# STorM32_NT_logger_v10.net
KiCad netlist of a schematic drawn in EAGLE
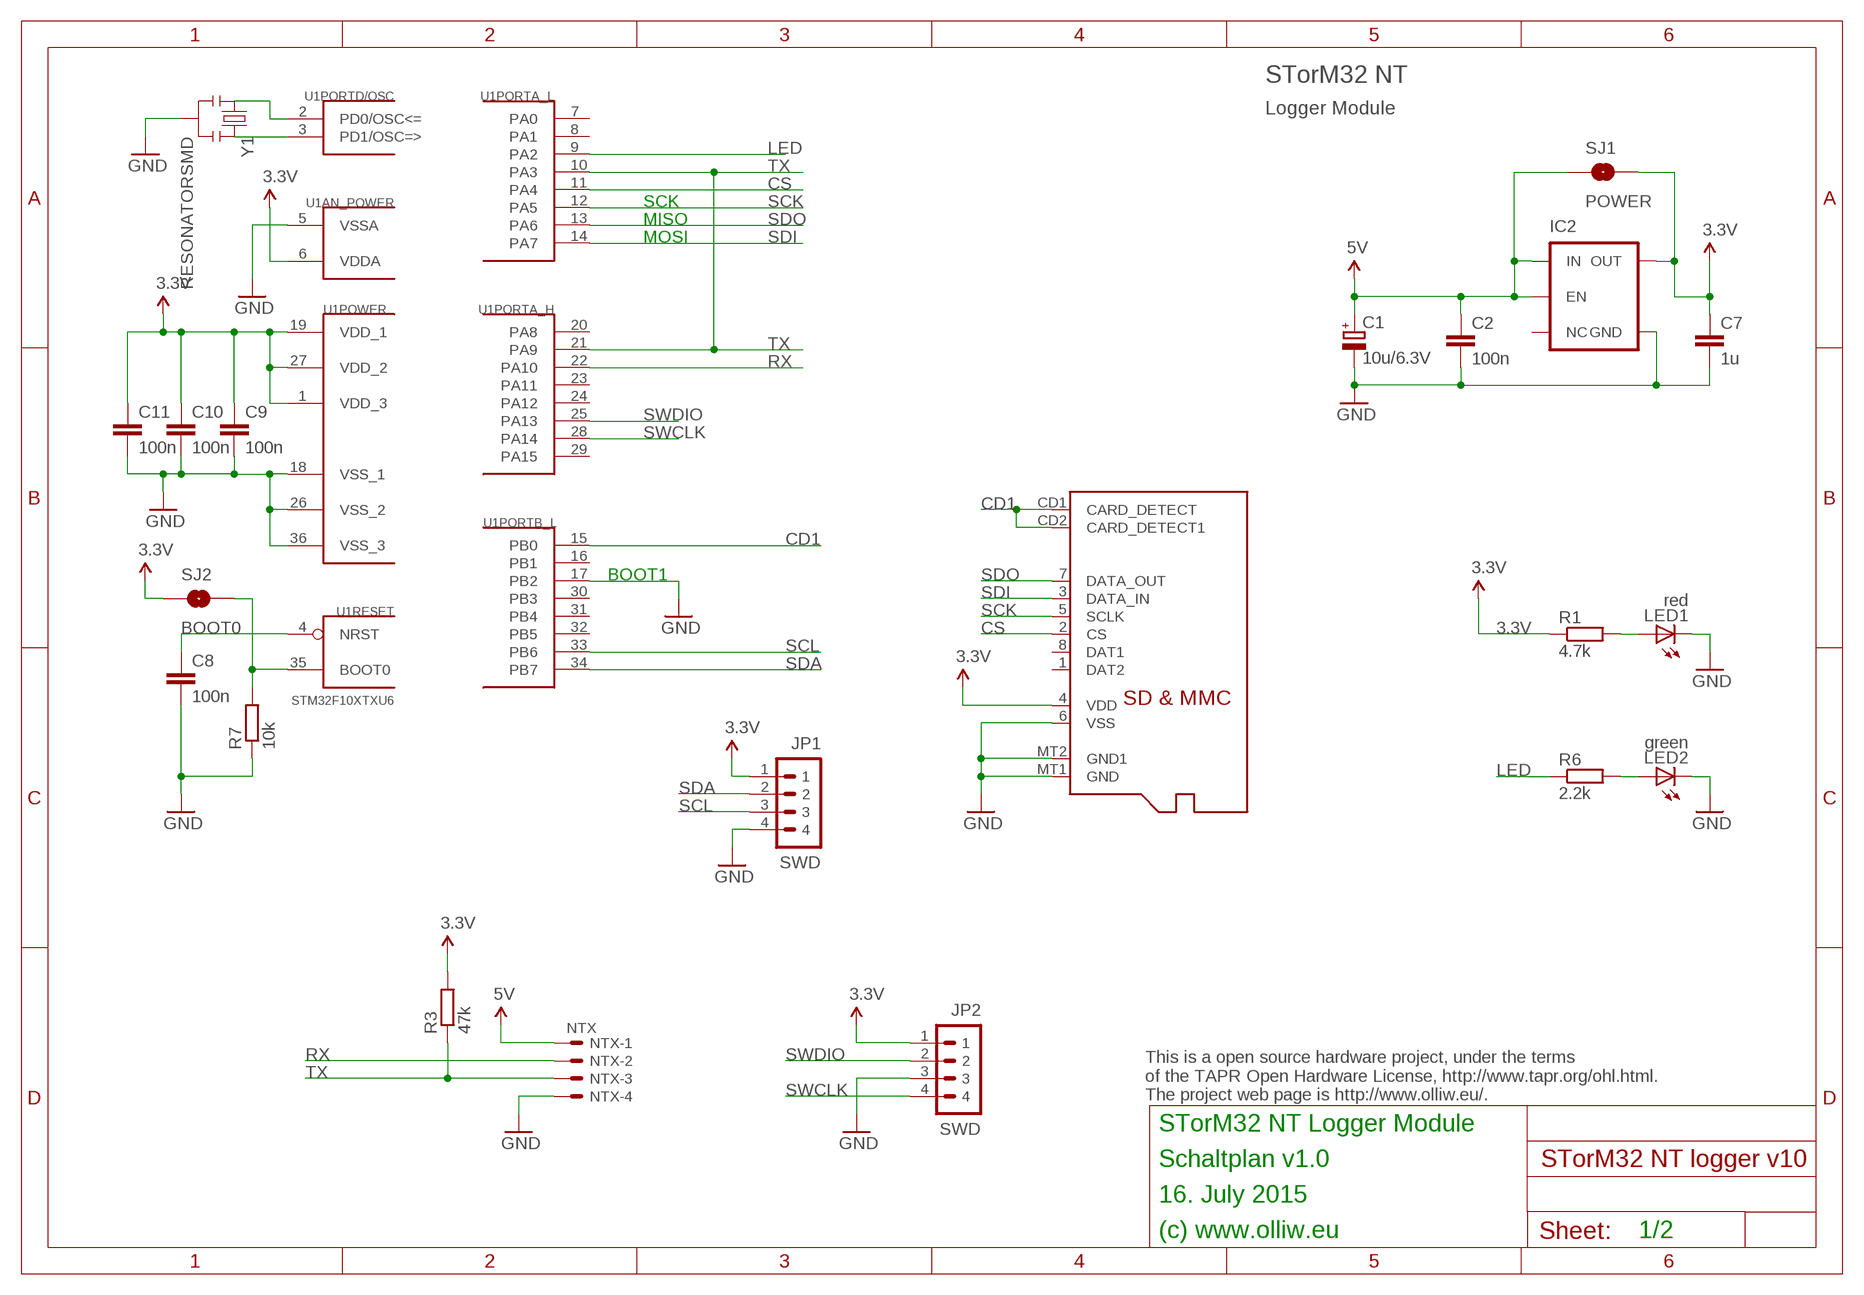
[diagram p0: schematic, sheet 1]

(export (version "E")
  (design (tool "Eeschema 10.0.6"))
  (components
    (comp (ref "C1")
      (value "10u/6.3V")
      (footprint "eagle-import:SMC_B")
      (libsource (lib "eagle-import") (part "CPOL-EUSMCB"))
    )
    (comp (ref "C2")
      (value "100n")
      (footprint "eagle-import:C0603")
      (libsource (lib "eagle-import") (part "C-EUC0603"))
    )
    (comp (ref "C7")
      (value "1u")
      (footprint "eagle-import:C0603")
      (libsource (lib "eagle-import") (part "C-EUC0603"))
    )
    (comp (ref "C8")
      (value "100n")
      (footprint "eagle-import:C0603")
      (libsource (lib "eagle-import") (part "C-EUC0603"))
    )
    (comp (ref "C9")
      (value "100n")
      (footprint "eagle-import:C0603")
      (libsource (lib "eagle-import") (part "C-EUC0603"))
    )
    (comp (ref "C10")
      (value "100n")
      (footprint "eagle-import:C0603")
      (libsource (lib "eagle-import") (part "C-EUC0603"))
    )
    (comp (ref "C11")
      (value "100n")
      (footprint "eagle-import:C0603")
      (libsource (lib "eagle-import") (part "C-EUC0603"))
    )
    (comp (ref "IC2")
      (value "V_REG_TPS76433SOT23-5")
      (footprint "eagle-import:SOT23-5")
      (libsource (lib "eagle-import") (part "V_REG_TPS76433SOT23-5"))
    )
    (comp (ref "JP1")
      (value "SWD")
      (footprint "eagle-import:4X1_1P27_OCT_BILEX")
      (libsource (lib "eagle-import") (part "P4X1_1P27-OCT_BILEX"))
    )
    (comp (ref "JP2")
      (value "SWD")
      (footprint "eagle-import:4X1_1P27_OCT_BILEX")
      (libsource (lib "eagle-import") (part "P4X1_1P27-OCT_BILEX"))
    )
    (comp (ref "LED1")
      (value "red")
      (footprint "eagle-import:CHIPLED_0603")
      (libsource (lib "eagle-import") (part "LEDCHIPLED_0603"))
    )
    (comp (ref "LED2")
      (value "green")
      (footprint "eagle-import:CHIPLED_0603")
      (libsource (lib "eagle-import") (part "LEDCHIPLED_0603"))
    )
    (comp (ref "NTX")
      (value "NTX")
      (footprint "eagle-import:SM04B-SRSS-TB")
      (libsource (lib "eagle-import") (part "?M04B-SRSS-TBS"))
    )
    (comp (ref "R1")
      (value "4.7k")
      (footprint "eagle-import:R0603")
      (libsource (lib "eagle-import") (part "R-EU_R0603"))
    )
    (comp (ref "R3")
      (value "47k")
      (footprint "eagle-import:R0603")
      (libsource (lib "eagle-import") (part "R-EU_R0603"))
    )
    (comp (ref "R6")
      (value "2.2k")
      (footprint "eagle-import:R0603")
      (libsource (lib "eagle-import") (part "R-EU_R0603"))
    )
    (comp (ref "R7")
      (value "10k")
      (footprint "eagle-import:R0603")
      (libsource (lib "eagle-import") (part "R-EU_R0603"))
    )
    (comp (ref "SJ1")
      (value "POWER")
      (footprint "eagle-import:SJ_2S-NO")
      (libsource (lib "eagle-import") (part "SOLDERJUMPERNO"))
    )
    (comp (ref "SJ2")
      (value "BOOT0")
      (footprint "eagle-import:SJ_2S-NO")
      (libsource (lib "eagle-import") (part "SOLDERJUMPERNO"))
    )
    (comp (ref "U$1")
      (value "MICROSD")
      (footprint "eagle-import:MICROSD")
      (libsource (lib "eagle-import") (part "MICROSD"))
    )
    (comp (ref "U1")
      (value "STM32F10XTXU6")
      (footprint "eagle-import:VFQFPN36")
      (libsource (lib "eagle-import") (part "STM32F10XTXU6"))
    )
    (comp (ref "Y1")
      (value "RESONATORSMD")
      (footprint "eagle-import:RESONATOR-SMD")
      (libsource (lib "eagle-import") (part "RESONATORSMD"))
    )
  )
  (nets
    (net (code "1") (name "/CD1") (class "Default")
      (node (ref "U$1") (pin "CD1") (pinfunction "CARD_DETECT_CD1") (pintype "passive"))
      (node (ref "U$1") (pin "CD2") (pinfunction "CARD_DETECT1_CD2") (pintype "passive"))
      (node (ref "U1") (pin "15") (pinfunction "PB0_15") (pintype "bidirectional"))
    )
    (net (code "2") (name "/CS") (class "Default")
      (node (ref "U$1") (pin "2") (pinfunction "CS_2") (pintype "input"))
      (node (ref "U1") (pin "11") (pinfunction "PA4_11") (pintype "bidirectional"))
    )
    (net (code "3") (name "/LED") (class "Default")
      (node (ref "R6") (pin "1") (pinfunction "1_1") (pintype "passive"))
      (node (ref "U1") (pin "9") (pinfunction "PA2_9") (pintype "bidirectional"))
    )
    (net (code "4") (name "/RX") (class "Default")
      (node (ref "NTX") (pin "2") (pinfunction "S_2") (pintype "passive"))
      (node (ref "U1") (pin "22") (pinfunction "PA10_22") (pintype "bidirectional"))
    )
    (net (code "5") (name "/SCK") (class "Default")
      (node (ref "U$1") (pin "5") (pinfunction "SCLK_5") (pintype "input"))
      (node (ref "U1") (pin "12") (pinfunction "PA5_12") (pintype "bidirectional"))
    )
    (net (code "6") (name "/SCL") (class "Default")
      (node (ref "JP1") (pin "3") (pinfunction "3_3") (pintype "passive"))
      (node (ref "U1") (pin "33") (pinfunction "PB6_33") (pintype "bidirectional"))
    )
    (net (code "7") (name "/SDA") (class "Default")
      (node (ref "JP1") (pin "2") (pinfunction "2_2") (pintype "passive"))
      (node (ref "U1") (pin "34") (pinfunction "PB7_34") (pintype "bidirectional"))
    )
    (net (code "8") (name "/SDI") (class "Default")
      (node (ref "U$1") (pin "3") (pinfunction "DATA_IN_3") (pintype "input"))
      (node (ref "U1") (pin "14") (pinfunction "PA7_14") (pintype "bidirectional"))
    )
    (net (code "9") (name "/SDO") (class "Default")
      (node (ref "U$1") (pin "7") (pinfunction "DATA_OUT_7") (pintype "output"))
      (node (ref "U1") (pin "13") (pinfunction "PA6_13") (pintype "bidirectional"))
    )
    (net (code "10") (name "/SWCLK") (class "Default")
      (node (ref "JP2") (pin "4") (pinfunction "4_4") (pintype "passive"))
      (node (ref "U1") (pin "28") (pinfunction "PA14_28") (pintype "bidirectional"))
    )
    (net (code "11") (name "/SWDIO") (class "Default")
      (node (ref "JP2") (pin "2") (pinfunction "2_2") (pintype "passive"))
      (node (ref "U1") (pin "25") (pinfunction "PA13_25") (pintype "bidirectional"))
    )
    (net (code "12") (name "/TX") (class "Default")
      (node (ref "NTX") (pin "3") (pinfunction "S_3") (pintype "passive"))
      (node (ref "R3") (pin "1") (pinfunction "1_1") (pintype "passive"))
      (node (ref "U1") (pin "10") (pinfunction "PA3_10") (pintype "bidirectional"))
      (node (ref "U1") (pin "21") (pinfunction "PA9_21") (pintype "bidirectional"))
    )
    (net (code "13") (name "3.3V") (class "Default")
      (node (ref "C10") (pin "1") (pinfunction "1_1") (pintype "passive"))
      (node (ref "C11") (pin "1") (pinfunction "1_1") (pintype "passive"))
      (node (ref "C7") (pin "1") (pinfunction "1_1") (pintype "passive"))
      (node (ref "C9") (pin "1") (pinfunction "1_1") (pintype "passive"))
      (node (ref "IC2") (pin "5") (pinfunction "OUT_5") (pintype "passive"))
      (node (ref "JP1") (pin "1") (pinfunction "1_1") (pintype "passive"))
      (node (ref "JP2") (pin "1") (pinfunction "1_1") (pintype "passive"))
      (node (ref "R1") (pin "1") (pinfunction "1_1") (pintype "passive"))
      (node (ref "R3") (pin "2") (pinfunction "2_2") (pintype "passive"))
      (node (ref "SJ1") (pin "2") (pinfunction "2_2") (pintype "passive"))
      (node (ref "SJ2") (pin "1") (pinfunction "1_1") (pintype "passive"))
      (node (ref "U$1") (pin "4") (pinfunction "VDD_4") (pintype "power_in"))
      (node (ref "U1") (pin "1") (pinfunction "VDD_3_1") (pintype "power_in"))
      (node (ref "U1") (pin "19") (pinfunction "VDD_1_19") (pintype "power_in"))
      (node (ref "U1") (pin "27") (pinfunction "VDD_2_27") (pintype "power_in"))
      (node (ref "U1") (pin "6") (pinfunction "VDDA_6") (pintype "power_in"))
    )
    (net (code "14") (name "5V") (class "Default")
      (node (ref "C1") (pin "+") (pinfunction "+_+") (pintype "passive"))
      (node (ref "C2") (pin "1") (pinfunction "1_1") (pintype "passive"))
      (node (ref "IC2") (pin "1") (pinfunction "IN_1") (pintype "input"))
      (node (ref "IC2") (pin "3") (pinfunction "EN_3") (pintype "input"))
      (node (ref "NTX") (pin "1") (pinfunction "S_1") (pintype "passive"))
      (node (ref "SJ1") (pin "1") (pinfunction "1_1") (pintype "passive"))
    )
    (net (code "15") (name "GND") (class "Default")
      (node (ref "C1") (pin "-") (pinfunction "-_-") (pintype "passive"))
      (node (ref "C10") (pin "2") (pinfunction "2_2") (pintype "passive"))
      (node (ref "C11") (pin "2") (pinfunction "2_2") (pintype "passive"))
      (node (ref "C2") (pin "2") (pinfunction "2_2") (pintype "passive"))
      (node (ref "C7") (pin "2") (pinfunction "2_2") (pintype "passive"))
      (node (ref "C8") (pin "2") (pinfunction "2_2") (pintype "passive"))
      (node (ref "C9") (pin "2") (pinfunction "2_2") (pintype "passive"))
      (node (ref "IC2") (pin "2") (pinfunction "GND_2") (pintype "input"))
      (node (ref "JP1") (pin "4") (pinfunction "4_4") (pintype "passive"))
      (node (ref "JP2") (pin "3") (pinfunction "3_3") (pintype "passive"))
      (node (ref "LED1") (pin "C") (pinfunction "C_C") (pintype "passive"))
      (node (ref "LED2") (pin "C") (pinfunction "C_C") (pintype "passive"))
      (node (ref "NTX") (pin "4") (pinfunction "S_4") (pintype "passive"))
      (node (ref "R7") (pin "1") (pinfunction "1_1") (pintype "passive"))
      (node (ref "U$1") (pin "6") (pinfunction "VSS_6") (pintype "power_in"))
      (node (ref "U$1") (pin "MT1") (pinfunction "GND_MT1") (pintype "power_in"))
      (node (ref "U$1") (pin "MT2") (pinfunction "GND1_MT2") (pintype "power_in"))
      (node (ref "U1") (pin "17") (pinfunction "PB2_17") (pintype "bidirectional"))
      (node (ref "U1") (pin "18") (pinfunction "VSS_1_18") (pintype "power_in"))
      (node (ref "U1") (pin "26") (pinfunction "VSS_2_26") (pintype "power_in"))
      (node (ref "U1") (pin "36") (pinfunction "VSS_3_36") (pintype "power_in"))
      (node (ref "U1") (pin "5") (pinfunction "VSSA_5") (pintype "power_in"))
      (node (ref "Y1") (pin "2") (pinfunction "2_2") (pintype "passive"))
    )
    (net (code "16") (name "Net-(LED1-PadA)") (class "Default")
      (node (ref "LED1") (pin "A") (pinfunction "A_A") (pintype "passive"))
      (node (ref "R1") (pin "2") (pinfunction "2_2") (pintype "passive"))
    )
    (net (code "17") (name "Net-(LED2-PadA)") (class "Default")
      (node (ref "LED2") (pin "A") (pinfunction "A_A") (pintype "passive"))
      (node (ref "R6") (pin "2") (pinfunction "2_2") (pintype "passive"))
    )
    (net (code "18") (name "Net-(U1E-PD0{slash}OSC<=)") (class "Default")
      (node (ref "U1") (pin "2") (pinfunction "PD0/OSC<=_2") (pintype "bidirectional"))
      (node (ref "Y1") (pin "1") (pinfunction "1_1") (pintype "passive"))
    )
    (net (code "19") (name "Net-(U1E-PD1{slash}OSC=>)") (class "Default")
      (node (ref "U1") (pin "3") (pinfunction "PD1/OSC=>_3") (pintype "bidirectional"))
      (node (ref "Y1") (pin "3") (pinfunction "3_3") (pintype "passive"))
    )
    (net (code "20") (name "Net-(U1G-BOOT0)") (class "Default")
      (node (ref "R7") (pin "2") (pinfunction "2_2") (pintype "passive"))
      (node (ref "SJ2") (pin "2") (pinfunction "2_2") (pintype "passive"))
      (node (ref "U1") (pin "35") (pinfunction "BOOT0_35") (pintype "input"))
    )
    (net (code "21") (name "Net-(U1G-NRST)") (class "Default")
      (node (ref "C8") (pin "1") (pinfunction "1_1") (pintype "passive"))
      (node (ref "U1") (pin "4") (pinfunction "NRST_4") (pintype "input"))
    )
    (net (code "22") (name "unconnected-(IC2-NC-Pad4)") (class "Default")
      (node (ref "IC2") (pin "4") (pinfunction "NC_4") (pintype "input"))
    )
    (net (code "23") (name "unconnected-(U$1-DAT1-Pad8)") (class "Default")
      (node (ref "U$1") (pin "8") (pinfunction "DAT1_8") (pintype "bidirectional"))
    )
    (net (code "24") (name "unconnected-(U$1-DAT2-Pad1)") (class "Default")
      (node (ref "U$1") (pin "1") (pinfunction "DAT2_1") (pintype "bidirectional"))
    )
    (net (code "25") (name "unconnected-(U1B-PA8-Pad20)") (class "Default")
      (node (ref "U1") (pin "20") (pinfunction "PA8_20") (pintype "bidirectional"))
    )
    (net (code "26") (name "unconnected-(U1B-PA11-Pad23)") (class "Default")
      (node (ref "U1") (pin "23") (pinfunction "PA11_23") (pintype "bidirectional"))
    )
    (net (code "27") (name "unconnected-(U1B-PA12-Pad24)") (class "Default")
      (node (ref "U1") (pin "24") (pinfunction "PA12_24") (pintype "bidirectional"))
    )
    (net (code "28") (name "unconnected-(U1B-PA15-Pad29)") (class "Default")
      (node (ref "U1") (pin "29") (pinfunction "PA15_29") (pintype "bidirectional"))
    )
    (net (code "29") (name "unconnected-(U1C-PA0-Pad7)") (class "Default")
      (node (ref "U1") (pin "7") (pinfunction "PA0_7") (pintype "bidirectional"))
    )
    (net (code "30") (name "unconnected-(U1C-PA1-Pad8)") (class "Default")
      (node (ref "U1") (pin "8") (pinfunction "PA1_8") (pintype "bidirectional"))
    )
    (net (code "31") (name "unconnected-(U1D-PB1-Pad16)") (class "Default")
      (node (ref "U1") (pin "16") (pinfunction "PB1_16") (pintype "bidirectional"))
    )
    (net (code "32") (name "unconnected-(U1D-PB3-Pad30)") (class "Default")
      (node (ref "U1") (pin "30") (pinfunction "PB3_30") (pintype "bidirectional"))
    )
    (net (code "33") (name "unconnected-(U1D-PB4-Pad31)") (class "Default")
      (node (ref "U1") (pin "31") (pinfunction "PB4_31") (pintype "bidirectional"))
    )
    (net (code "34") (name "unconnected-(U1D-PB5-Pad32)") (class "Default")
      (node (ref "U1") (pin "32") (pinfunction "PB5_32") (pintype "bidirectional"))
    )
  )
)
